# Power.net
KiCad netlist of a schematic drawn in Altium Designer
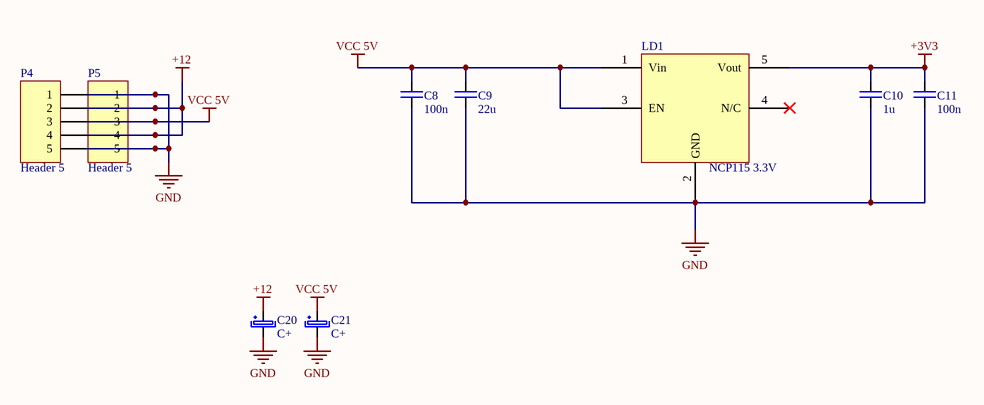
[diagram p0: Power.SchDoc]

(export (version "E")
  (design (tool "Eeschema 10.0.6"))
  (components
    (comp (ref "C8")
      (value "100n")
      (footprint "R1005_0402i_L")
      (description "Capacitor")
      (libsource (lib "General") (part "C"))
    )
    (comp (ref "C9")
      (value "22u")
      (footprint "C1608_0603I_L")
      (description "Capacitor")
      (libsource (lib "General") (part "C"))
    )
    (comp (ref "C10")
      (value "1u")
      (footprint "R1005_0402i_L")
      (description "Capacitor")
      (libsource (lib "General") (part "C"))
    )
    (comp (ref "C11")
      (value "100n")
      (footprint "R1005_0402i_L")
      (description "Capacitor")
      (libsource (lib "General") (part "C"))
    )
    (comp (ref "C20")
      (value "C+")
      (footprint "C AlElko 5x11 R2")
      (description "Capacitor Polarized")
      (libsource (lib "General") (part "C+"))
    )
    (comp (ref "C21")
      (value "C+")
      (footprint "C AlElko 5x11 R2")
      (description "Capacitor Polarized")
      (libsource (lib "General") (part "C+"))
    )
    (comp (ref "LD1")
      (value "NCP115 3.3V")
      (footprint "TSOP95P280X110-6L")
      (libsource (lib "components_library") (part "NCP115 3.3V"))
    )
    (comp (ref "P4")
      (value "Header 5")
      (footprint "HDR1X5")
      (description "Header, 5-Pin")
      (fields (field (name "PUBLISHER") "Altium Limited"))
      (libsource (lib "Miscellaneous Connectors") (part "Header 5"))
    )
    (comp (ref "P5")
      (value "Header 5")
      (footprint "HDR1X5")
      (description "Header, 5-Pin")
      (fields (field (name "PUBLISHER") "Altium Limited"))
      (libsource (lib "Miscellaneous Connectors") (part "Header 5"))
    )
  )
  (nets
    (net (code "1") (name "+3V3") (class "Default")
      (node (ref "C10") (pin "1") (pinfunction "1_1") (pintype "passive"))
      (node (ref "C11") (pin "1") (pinfunction "1_1") (pintype "passive"))
      (node (ref "LD1") (pin "5") (pinfunction "Vout_5") (pintype "passive"))
    )
    (net (code "2") (name "+12") (class "Default")
      (node (ref "C20") (pin "1") (pinfunction "1_1") (pintype "passive"))
      (node (ref "P4") (pin "2") (pinfunction "2_2") (pintype "passive"))
      (node (ref "P4") (pin "4") (pinfunction "4_4") (pintype "passive"))
      (node (ref "P5") (pin "2") (pinfunction "2_2") (pintype "passive"))
      (node (ref "P5") (pin "4") (pinfunction "4_4") (pintype "passive"))
    )
    (net (code "3") (name "GND") (class "Default")
      (node (ref "C10") (pin "2") (pinfunction "2_2") (pintype "passive"))
      (node (ref "C11") (pin "2") (pinfunction "2_2") (pintype "passive"))
      (node (ref "C20") (pin "2") (pinfunction "2_2") (pintype "passive"))
      (node (ref "C21") (pin "2") (pinfunction "2_2") (pintype "passive"))
      (node (ref "C8") (pin "2") (pinfunction "2_2") (pintype "passive"))
      (node (ref "C9") (pin "2") (pinfunction "2_2") (pintype "passive"))
      (node (ref "LD1") (pin "2") (pinfunction "GND_2") (pintype "passive"))
      (node (ref "P4") (pin "1") (pinfunction "1_1") (pintype "passive"))
      (node (ref "P4") (pin "5") (pinfunction "5_5") (pintype "passive"))
      (node (ref "P5") (pin "1") (pinfunction "1_1") (pintype "passive"))
      (node (ref "P5") (pin "5") (pinfunction "5_5") (pintype "passive"))
    )
    (net (code "4") (name "VCC 5V") (class "Default")
      (node (ref "C21") (pin "1") (pinfunction "1_1") (pintype "passive"))
      (node (ref "C8") (pin "1") (pinfunction "1_1") (pintype "passive"))
      (node (ref "C9") (pin "1") (pinfunction "1_1") (pintype "passive"))
      (node (ref "LD1") (pin "1") (pinfunction "Vin_1") (pintype "passive"))
      (node (ref "LD1") (pin "3") (pinfunction "EN_3") (pintype "passive"))
      (node (ref "P4") (pin "3") (pinfunction "3_3") (pintype "passive"))
      (node (ref "P5") (pin "3") (pinfunction "3_3") (pintype "passive"))
    )
    (net (code "5") (name "unconnected-(LD1-N{slash}C-Pad4)") (class "Default")
      (node (ref "LD1") (pin "4") (pinfunction "N/C_4") (pintype "passive+no_connect"))
    )
  )
)
